# ESP32_Dev_Board.net
KiCad netlist of a schematic drawn in EasyEDA Pro
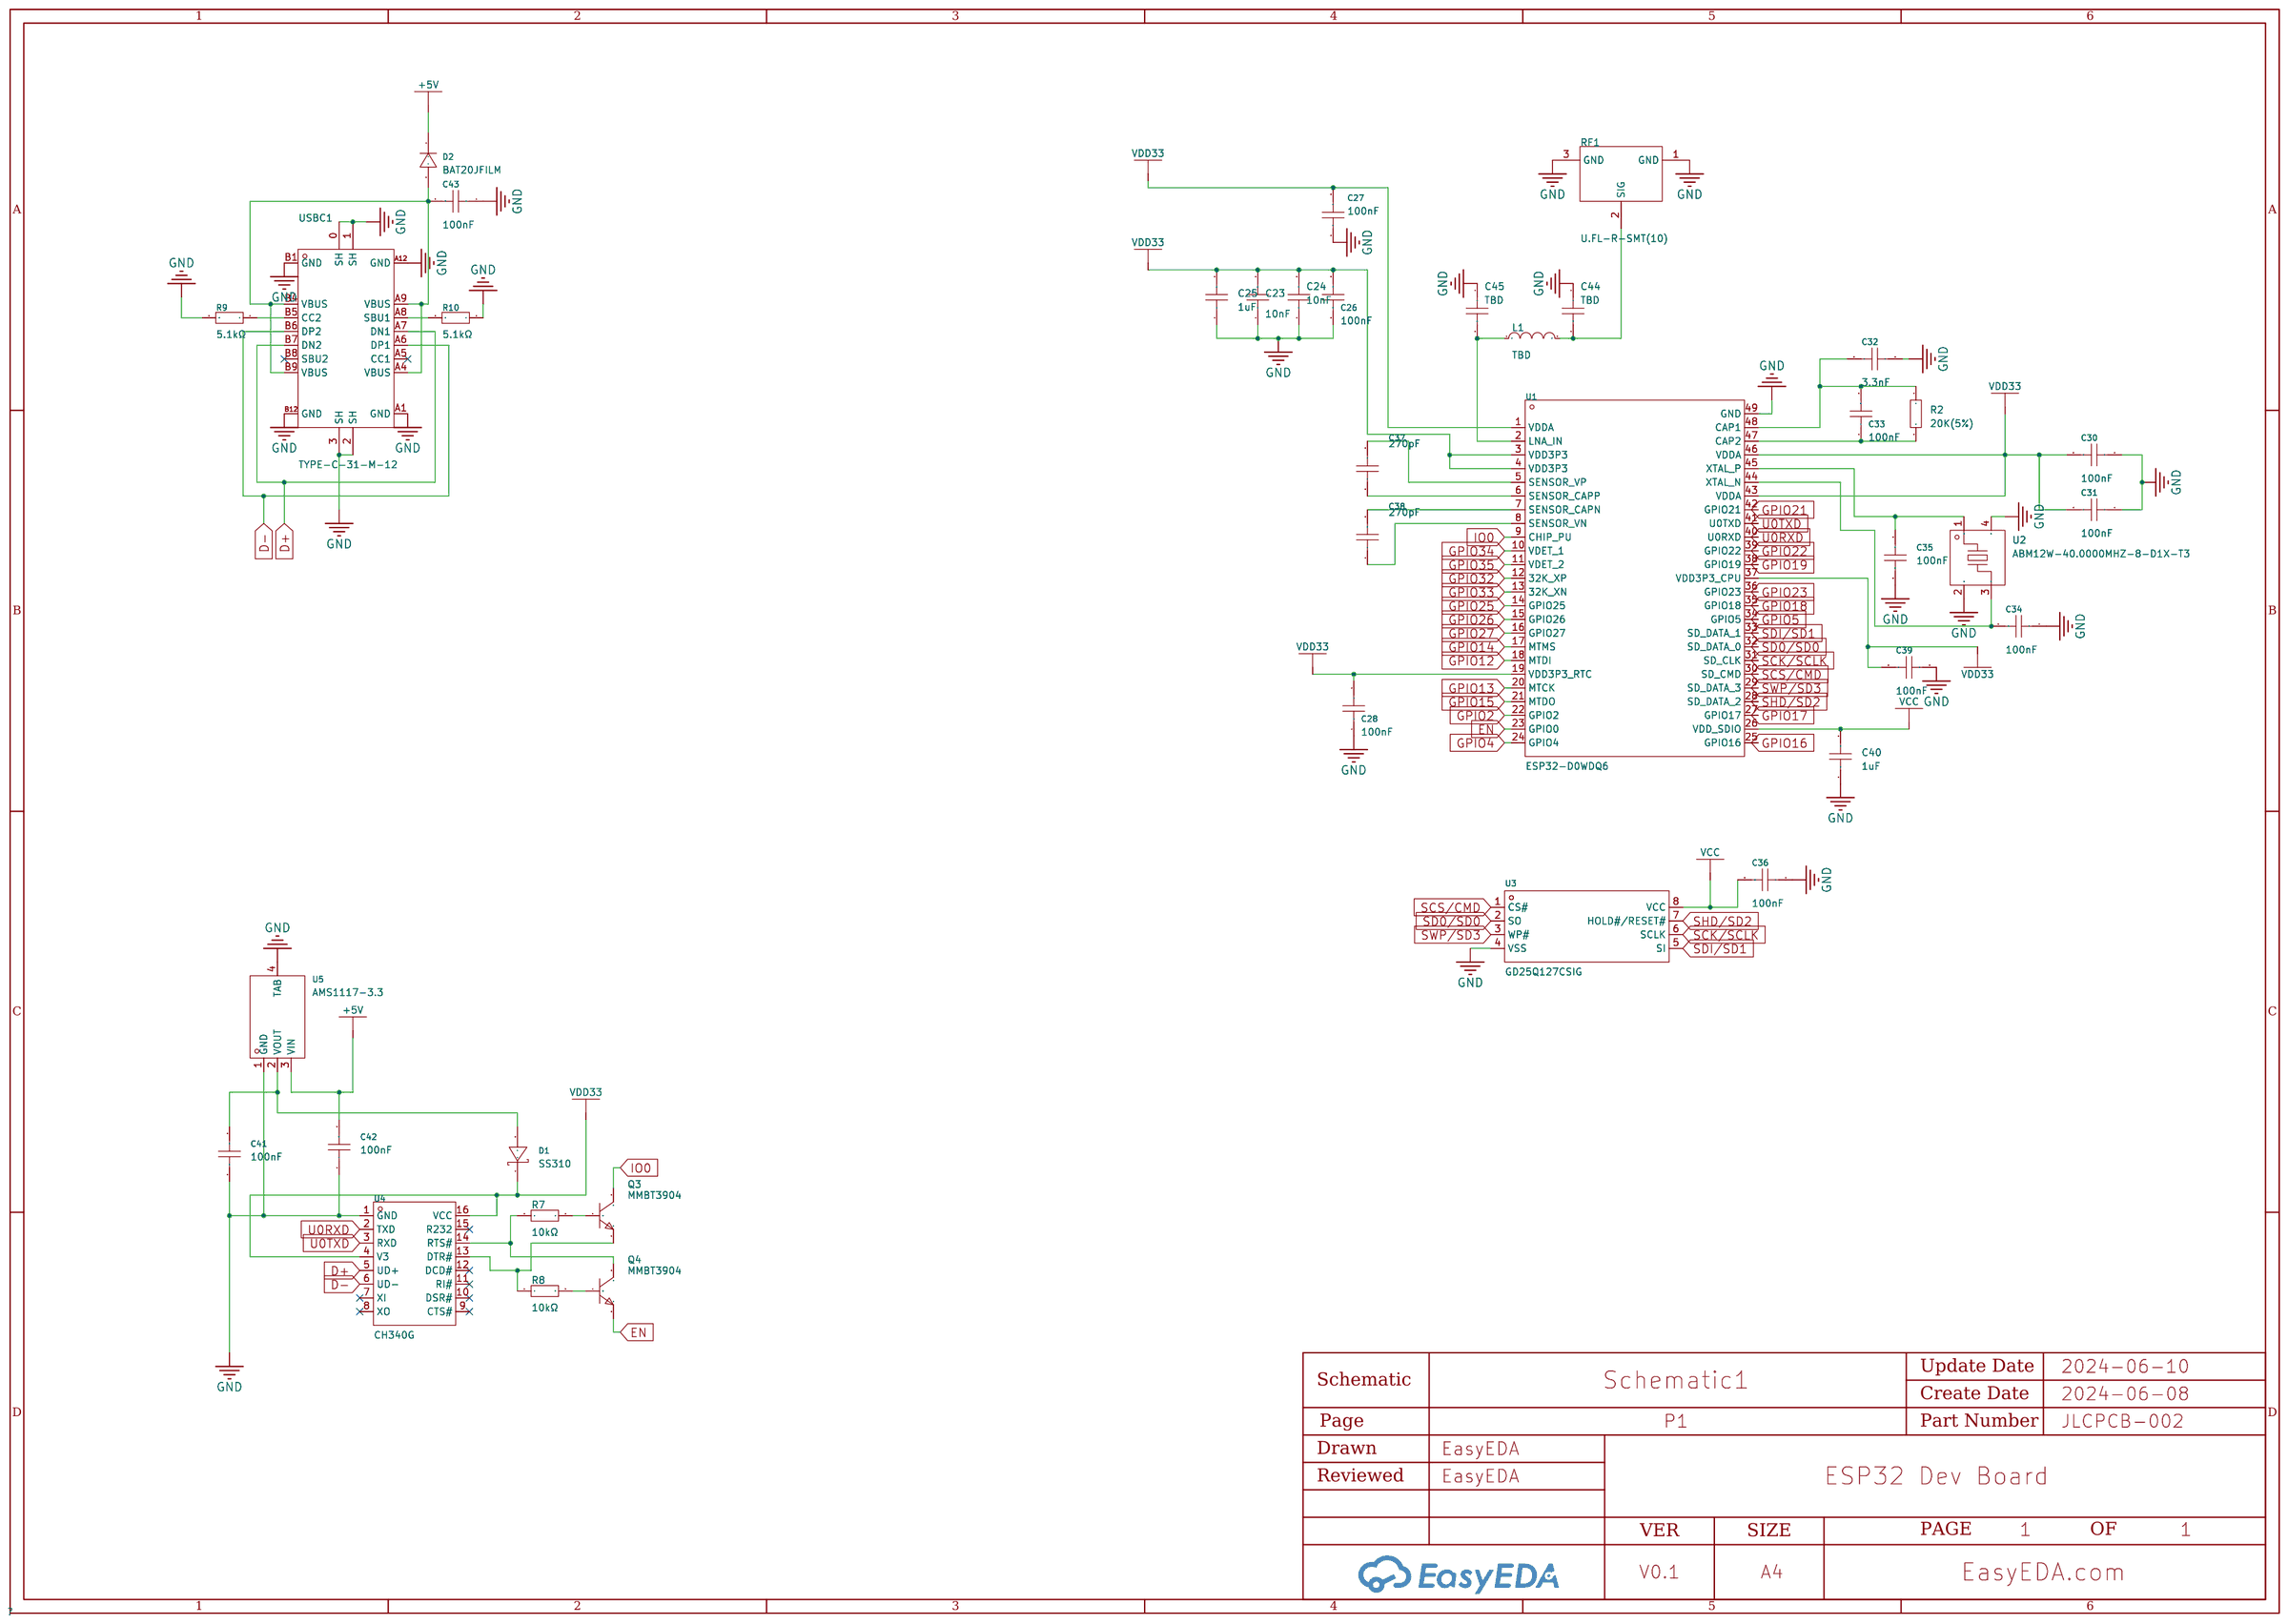
[diagram p0: schematic sheet]

(export (version "E")
  (design (tool "Eeschema 10.0.6"))
  (components
    (comp (ref "C23")
      (value "10nF")
      (footprint "easyedapro:C0402")
      (fields (field (name "Manufacturer Part") "0402B103K160NT") (field (name "Manufacturer") "FH(风华)"))
      (libsource (lib "easyedapro") (part "0402B103K160NT"))
    )
    (comp (ref "C24")
      (value "10nF")
      (footprint "easyedapro:C0402")
      (fields (field (name "Manufacturer Part") "0402B103K160NT") (field (name "Manufacturer") "FH(风华)"))
      (libsource (lib "easyedapro") (part "0402B103K160NT"))
    )
    (comp (ref "C25")
      (value "1uF")
      (footprint "easyedapro:C0402")
      (fields
        (field (name "Manufacturer Part") "C0402X5R105K350NT")
        (field (name "Manufacturer") "SANYEAR(叁叶源)")
      )
      (libsource (lib "easyedapro") (part "C0402X5R105K350NT"))
    )
    (comp (ref "C26")
      (value "100nF")
      (footprint "easyedapro:C0402")
      (fields
        (field (name "Manufacturer Part") "CT41G-0402-2X1-16V-0.1μF-K(N)")
        (field (name "Manufacturer") "TORCH(火炬)")
      )
      (libsource (lib "easyedapro") (part "CT41G-0402-2X1-16V-0.1μF-K(N)"))
    )
    (comp (ref "C27")
      (value "100nF")
      (footprint "easyedapro:C0402")
      (fields
        (field (name "Manufacturer Part") "CT41G-0402-2X1-16V-0.1μF-K(N)")
        (field (name "Manufacturer") "TORCH(火炬)")
      )
      (libsource (lib "easyedapro") (part "CT41G-0402-2X1-16V-0.1μF-K(N)"))
    )
    (comp (ref "C28")
      (value "100nF")
      (footprint "easyedapro:C0402")
      (fields
        (field (name "Manufacturer Part") "CT41G-0402-2X1-16V-0.1μF-K(N)")
        (field (name "Manufacturer") "TORCH(火炬)")
      )
      (libsource (lib "easyedapro") (part "CT41G-0402-2X1-16V-0.1μF-K(N)"))
    )
    (comp (ref "C30")
      (value "100nF")
      (footprint "easyedapro:C0402")
      (fields
        (field (name "Manufacturer Part") "CT41G-0402-2X1-16V-0.1μF-K(N)")
        (field (name "Manufacturer") "TORCH(火炬)")
      )
      (libsource (lib "easyedapro") (part "CT41G-0402-2X1-16V-0.1μF-K(N)"))
    )
    (comp (ref "C31")
      (value "100nF")
      (footprint "easyedapro:C0402")
      (fields
        (field (name "Manufacturer Part") "CT41G-0402-2X1-16V-0.1μF-K(N)")
        (field (name "Manufacturer") "TORCH(火炬)")
      )
      (libsource (lib "easyedapro") (part "CT41G-0402-2X1-16V-0.1μF-K(N)"))
    )
    (comp (ref "C32")
      (value "3.3nF")
      (footprint "easyedapro:C0402")
      (fields (field (name "Manufacturer Part") "04025C332KAT2A") (field (name "Manufacturer") "Kyocera AVX"))
      (libsource (lib "easyedapro") (part "04025C332KAT2A"))
    )
    (comp (ref "C33")
      (value "100nF")
      (footprint "easyedapro:C0402")
      (fields
        (field (name "Manufacturer Part") "CT41G-0402-2X1-16V-0.1μF-K(N)")
        (field (name "Manufacturer") "TORCH(火炬)")
      )
      (libsource (lib "easyedapro") (part "CT41G-0402-2X1-16V-0.1μF-K(N)"))
    )
    (comp (ref "C34")
      (value "100nF")
      (footprint "easyedapro:C0402")
      (fields
        (field (name "Manufacturer Part") "CT41G-0402-2X1-16V-0.1μF-K(N)")
        (field (name "Manufacturer") "TORCH(火炬)")
      )
      (libsource (lib "easyedapro") (part "CT41G-0402-2X1-16V-0.1μF-K(N)"))
    )
    (comp (ref "C35")
      (value "100nF")
      (footprint "easyedapro:C0402")
      (fields
        (field (name "Manufacturer Part") "CT41G-0402-2X1-16V-0.1μF-K(N)")
        (field (name "Manufacturer") "TORCH(火炬)")
      )
      (libsource (lib "easyedapro") (part "CT41G-0402-2X1-16V-0.1μF-K(N)"))
    )
    (comp (ref "C36")
      (value "100nF")
      (footprint "easyedapro:C0402")
      (fields
        (field (name "Manufacturer Part") "CT41G-0402-2X1-16V-0.1μF-K(N)")
        (field (name "Manufacturer") "TORCH(火炬)")
      )
      (libsource (lib "easyedapro") (part "CT41G-0402-2X1-16V-0.1μF-K(N)"))
    )
    (comp (ref "C37")
      (value "270pF")
      (footprint "easyedapro:C0402")
      (fields (field (name "Manufacturer Part") "0402N271J500CT") (field (name "Manufacturer") "Walsin(华新科)"))
      (libsource (lib "easyedapro") (part "0402N271J500CT"))
    )
    (comp (ref "C38")
      (value "270pF")
      (footprint "easyedapro:C0402")
      (fields (field (name "Manufacturer Part") "0402N271J500CT") (field (name "Manufacturer") "Walsin(华新科)"))
      (libsource (lib "easyedapro") (part "0402N271J500CT"))
    )
    (comp (ref "C39")
      (value "100nF")
      (footprint "easyedapro:C0402")
      (fields
        (field (name "Manufacturer Part") "CT41G-0402-2X1-16V-0.1μF-K(N)")
        (field (name "Manufacturer") "TORCH(火炬)")
      )
      (libsource (lib "easyedapro") (part "CT41G-0402-2X1-16V-0.1μF-K(N)"))
    )
    (comp (ref "C40")
      (value "1uF")
      (footprint "easyedapro:C0402")
      (fields
        (field (name "Manufacturer Part") "C0402X5R105K350NT")
        (field (name "Manufacturer") "SANYEAR(叁叶源)")
      )
      (libsource (lib "easyedapro") (part "C0402X5R105K350NT"))
    )
    (comp (ref "C41")
      (value "100nF")
      (footprint "easyedapro:C0402")
      (fields
        (field (name "Manufacturer Part") "CT41G-0402-2X1-16V-0.1μF-K(N)")
        (field (name "Manufacturer") "TORCH(火炬)")
      )
      (libsource (lib "easyedapro") (part "CT41G-0402-2X1-16V-0.1μF-K(N)"))
    )
    (comp (ref "C42")
      (value "100nF")
      (footprint "easyedapro:C0402")
      (fields
        (field (name "Manufacturer Part") "CT41G-0402-2X1-16V-0.1μF-K(N)")
        (field (name "Manufacturer") "TORCH(火炬)")
      )
      (libsource (lib "easyedapro") (part "CT41G-0402-2X1-16V-0.1μF-K(N)"))
    )
    (comp (ref "C43")
      (value "100nF")
      (footprint "easyedapro:C0402")
      (fields
        (field (name "Manufacturer Part") "CT41G-0402-2X1-16V-0.1μF-K(N)")
        (field (name "Manufacturer") "TORCH(火炬)")
      )
      (libsource (lib "easyedapro") (part "CT41G-0402-2X1-16V-0.1μF-K(N)"))
    )
    (comp (ref "C44")
      (value "TBD")
      (footprint "easyedapro:C0603")
      (libsource (lib "easyedapro") (part "CAP"))
    )
    (comp (ref "C45")
      (value "TBD")
      (footprint "easyedapro:C0603")
      (libsource (lib "easyedapro") (part "CAP"))
    )
    (comp (ref "D1")
      (value "SS310")
      (footprint "easyedapro:SMA_L4.4-W2.8-LS5.4-RD")
      (fields (field (name "Manufacturer") "晶导微电子"))
      (libsource (lib "easyedapro") (part "SS310_C116705"))
    )
    (comp (ref "D2")
      (value "BAT20JFILM")
      (footprint "easyedapro:SOD-323_L1.8-W1.3-LS2.5-RD")
      (fields (field (name "Manufacturer") "ST(意法半导体)"))
      (libsource (lib "easyedapro") (part "BAT20JFILM"))
    )
    (comp (ref "L1") (value "TBD") (footprint "easyedapro:L0603") (libsource (lib "easyedapro") (part "电感")))
    (comp (ref "Q3")
      (value "MMBT3904")
      (footprint "easyedapro:SOT-23-3_L2.9-W1.3-P1.90-LS2.4-BR")
      (fields (field (name "Manufacturer") "FMS(美丽微)"))
      (libsource (lib "easyedapro") (part "MMBT3904_C163254"))
    )
    (comp (ref "Q4")
      (value "MMBT3904")
      (footprint "easyedapro:SOT-23-3_L2.9-W1.3-P1.90-LS2.4-BR")
      (fields (field (name "Manufacturer") "FMS(美丽微)"))
      (libsource (lib "easyedapro") (part "MMBT3904_C163254"))
    )
    (comp (ref "R2")
      (value "20K(5%)")
      (footprint "easyedapro:R0603")
      (libsource (lib "easyedapro") (part "Res"))
    )
    (comp (ref "R7")
      (value "10kΩ")
      (footprint "easyedapro:R0402")
      (fields (field (name "Manufacturer Part") "RMC040210KFN") (field (name "Manufacturer") "Tyohm(幸亚电阻)"))
      (libsource (lib "easyedapro") (part "RMC040210K1%N"))
    )
    (comp (ref "R8")
      (value "10kΩ")
      (footprint "easyedapro:R0402")
      (fields (field (name "Manufacturer Part") "RMC040210KFN") (field (name "Manufacturer") "Tyohm(幸亚电阻)"))
      (libsource (lib "easyedapro") (part "RMC040210K1%N"))
    )
    (comp (ref "R9")
      (value "5.1kΩ")
      (footprint "easyedapro:R0402")
      (fields (field (name "Manufacturer Part") "RMC04025.1K1%N") (field (name "Manufacturer") "Tyohm(幸亚电阻)"))
      (libsource (lib "easyedapro") (part "RMC04025.1K1%N"))
    )
    (comp (ref "R10")
      (value "5.1kΩ")
      (footprint "easyedapro:R0402")
      (fields (field (name "Manufacturer Part") "RMC04025.1K1%N") (field (name "Manufacturer") "Tyohm(幸亚电阻)"))
      (libsource (lib "easyedapro") (part "RMC04025.1K1%N"))
    )
    (comp (ref "RF1")
      (value "U.FL-R-SMT(10)")
      (footprint "easyedapro:ANT-SMD_UFL-R-SMT01")
      (fields (field (name "Manufacturer") "HRS(广濑)"))
      (libsource (lib "easyedapro") (part "U.FL-R-SMT(10)"))
    )
    (comp (ref "U1")
      (value "ESP32-D0WDQ6")
      (footprint "easyedapro:QFN-48_L6.0-W6.0-P0.40-BL-EP3.8")
      (fields (field (name "Manufacturer") "ESPRESSIF(乐鑫)"))
      (libsource (lib "easyedapro") (part "ESP32-D0WDQ6"))
    )
    (comp (ref "U2")
      (value "ABM12W-40.0000MHZ-8-D1X-T3")
      (footprint "easyedapro:CRYSTAL-SMD_4P-L1.6-W1.2-BL")
      (libsource (lib "easyedapro") (part "ABM12W-40.0000MHZ-8-D1X-T3"))
    )
    (comp (ref "U3")
      (value "GD25Q127CSIG")
      (footprint "easyedapro:SOP-8_L5.3-W5.3-P1.27-LS8.0-BL")
      (fields (field (name "Manufacturer") "GigaDevice(兆易创新)"))
      (libsource (lib "easyedapro") (part "GD25Q127CSIG"))
    )
    (comp (ref "U4")
      (value "CH340G")
      (footprint "easyedapro:SOIC-16_L9.9-W3.9-P1.27-LS6.0-BL")
      (fields (field (name "Manufacturer") "WCH(南京沁恒)"))
      (libsource (lib "easyedapro") (part "CH340G"))
    )
    (comp (ref "U5")
      (value "AMS1117-3.3")
      (footprint "easyedapro:SOT-223-3_L6.5-W3.4-P2.30-LS7.0-BR")
      (fields (field (name "Manufacturer") "PUOLOP(迪浦)"))
      (libsource (lib "easyedapro") (part "AMS1117-3.3_C351784"))
    )
    (comp (ref "USBC1")
      (value "TYPE-C-31-M-12")
      (footprint "easyedapro:USB-C_SMD-TYPE-C-31-M-12")
      (fields (field (name "Manufacturer") "韩国韩荣"))
      (libsource (lib "easyedapro") (part "TYPE-C-31-M-12"))
    )
  )
  (nets
    (net (code "1") (name "+5V") (class "Default")
      (node (ref "C42") (pin "2") (pinfunction "2_2") (pintype "input"))
      (node (ref "D2") (pin "1") (pinfunction "K_1") (pintype "input"))
      (node (ref "U5") (pin "3") (pinfunction "VIN_3") (pintype "input"))
    )
    (net (code "2") (name "D+") (class "Default")
      (node (ref "U4") (pin "5") (pinfunction "UD+_5") (pintype "input"))
      (node (ref "USBC1") (pin "A7") (pinfunction "DN1_A7") (pintype "unspecified"))
      (node (ref "USBC1") (pin "B7") (pinfunction "DN2_B7") (pintype "unspecified"))
    )
    (net (code "3") (name "D-") (class "Default")
      (node (ref "U4") (pin "6") (pinfunction "UD-_6") (pintype "input"))
      (node (ref "USBC1") (pin "A6") (pinfunction "DP1_A6") (pintype "unspecified"))
      (node (ref "USBC1") (pin "B6") (pinfunction "DP2_B6") (pintype "unspecified"))
    )
    (net (code "4") (name "EN") (class "Default")
      (node (ref "Q4") (pin "2") (pinfunction "E_2") (pintype "unspecified"))
      (node (ref "U1") (pin "23") (pinfunction "GPIO0_23") (pintype "input"))
    )
    (net (code "5") (name "GND") (class "Default")
      (node (ref "C23") (pin "1") (pinfunction "1_1") (pintype "unspecified"))
      (node (ref "C24") (pin "1") (pinfunction "1_1") (pintype "unspecified"))
      (node (ref "C25") (pin "1") (pinfunction "1_1") (pintype "input"))
      (node (ref "C26") (pin "1") (pinfunction "1_1") (pintype "input"))
      (node (ref "C27") (pin "1") (pinfunction "1_1") (pintype "input"))
      (node (ref "C28") (pin "1") (pinfunction "1_1") (pintype "input"))
      (node (ref "C30") (pin "1") (pinfunction "1_1") (pintype "input"))
      (node (ref "C31") (pin "1") (pinfunction "1_1") (pintype "input"))
      (node (ref "C32") (pin "1") (pinfunction "1_1") (pintype "input"))
      (node (ref "C34") (pin "1") (pinfunction "1_1") (pintype "input"))
      (node (ref "C35") (pin "2") (pinfunction "2_2") (pintype "input"))
      (node (ref "C36") (pin "1") (pinfunction "1_1") (pintype "input"))
      (node (ref "C39") (pin "1") (pinfunction "1_1") (pintype "input"))
      (node (ref "C40") (pin "1") (pinfunction "1_1") (pintype "input"))
      (node (ref "C41") (pin "1") (pinfunction "1_1") (pintype "input"))
      (node (ref "C42") (pin "1") (pinfunction "1_1") (pintype "input"))
      (node (ref "C43") (pin "1") (pinfunction "1_1") (pintype "input"))
      (node (ref "C44") (pin "1") (pinfunction "1_1") (pintype "input"))
      (node (ref "C45") (pin "1") (pinfunction "1_1") (pintype "input"))
      (node (ref "R10") (pin "1") (pinfunction "1_1") (pintype "input"))
      (node (ref "R9") (pin "2") (pinfunction "2_2") (pintype "input"))
      (node (ref "RF1") (pin "1") (pinfunction "GND_1") (pintype "unspecified"))
      (node (ref "RF1") (pin "3") (pinfunction "GND_3") (pintype "unspecified"))
      (node (ref "U1") (pin "49") (pinfunction "GND_49") (pintype "input"))
      (node (ref "U2") (pin "2") (pinfunction "GND_2") (pintype "input"))
      (node (ref "U2") (pin "4") (pinfunction "GND_4") (pintype "input"))
      (node (ref "U3") (pin "4") (pinfunction "VSS_4") (pintype "input"))
      (node (ref "U4") (pin "1") (pinfunction "GND_1") (pintype "input"))
      (node (ref "U5") (pin "1") (pinfunction "GND_1") (pintype "input"))
      (node (ref "U5") (pin "4") (pinfunction "TAB_4") (pintype "input"))
      (node (ref "USBC1") (pin "0") (pinfunction "SH_0") (pintype "unspecified"))
      (node (ref "USBC1") (pin "1") (pinfunction "SH_1") (pintype "unspecified"))
      (node (ref "USBC1") (pin "2") (pinfunction "SH_2") (pintype "unspecified"))
      (node (ref "USBC1") (pin "3") (pinfunction "SH_3") (pintype "unspecified"))
      (node (ref "USBC1") (pin "A1") (pinfunction "GND_A1") (pintype "unspecified"))
      (node (ref "USBC1") (pin "A12") (pinfunction "GND_A12") (pintype "unspecified"))
      (node (ref "USBC1") (pin "B1") (pinfunction "GND_B1") (pintype "unspecified"))
      (node (ref "USBC1") (pin "B12") (pinfunction "GND_B12") (pintype "unspecified"))
    )
    (net (code "6") (name "GPIO2") (class "Default")
      (node (ref "U1") (pin "22") (pinfunction "GPIO2_22") (pintype "input"))
    )
    (net (code "7") (name "GPIO4") (class "Default")
      (node (ref "U1") (pin "24") (pinfunction "GPIO4_24") (pintype "input"))
    )
    (net (code "8") (name "GPIO5") (class "Default")
      (node (ref "U1") (pin "34") (pinfunction "GPIO5_34") (pintype "input"))
    )
    (net (code "9") (name "GPIO12") (class "Default")
      (node (ref "U1") (pin "18") (pinfunction "MTDI_18") (pintype "input"))
    )
    (net (code "10") (name "GPIO13") (class "Default")
      (node (ref "U1") (pin "20") (pinfunction "MTCK_20") (pintype "input"))
    )
    (net (code "11") (name "GPIO14") (class "Default")
      (node (ref "U1") (pin "17") (pinfunction "MTMS_17") (pintype "input"))
    )
    (net (code "12") (name "GPIO15") (class "Default")
      (node (ref "U1") (pin "21") (pinfunction "MTDO_21") (pintype "input"))
    )
    (net (code "13") (name "GPIO16") (class "Default")
      (node (ref "U1") (pin "25") (pinfunction "GPIO16_25") (pintype "input"))
    )
    (net (code "14") (name "GPIO17") (class "Default")
      (node (ref "U1") (pin "27") (pinfunction "GPIO17_27") (pintype "input"))
    )
    (net (code "15") (name "GPIO18") (class "Default")
      (node (ref "U1") (pin "35") (pinfunction "GPIO18_35") (pintype "input"))
    )
    (net (code "16") (name "GPIO19") (class "Default")
      (node (ref "U1") (pin "38") (pinfunction "GPIO19_38") (pintype "input"))
    )
    (net (code "17") (name "GPIO21") (class "Default")
      (node (ref "U1") (pin "42") (pinfunction "GPIO21_42") (pintype "input"))
    )
    (net (code "18") (name "GPIO22") (class "Default")
      (node (ref "U1") (pin "39") (pinfunction "GPIO22_39") (pintype "input"))
    )
    (net (code "19") (name "GPIO23") (class "Default")
      (node (ref "U1") (pin "36") (pinfunction "GPIO23_36") (pintype "input"))
    )
    (net (code "20") (name "GPIO25") (class "Default")
      (node (ref "U1") (pin "14") (pinfunction "GPIO25_14") (pintype "input"))
    )
    (net (code "21") (name "GPIO26") (class "Default")
      (node (ref "U1") (pin "15") (pinfunction "GPIO26_15") (pintype "input"))
    )
    (net (code "22") (name "GPIO27") (class "Default")
      (node (ref "U1") (pin "16") (pinfunction "GPIO27_16") (pintype "input"))
    )
    (net (code "23") (name "GPIO32") (class "Default")
      (node (ref "U1") (pin "12") (pinfunction "32K_XP_12") (pintype "input"))
    )
    (net (code "24") (name "GPIO33") (class "Default")
      (node (ref "U1") (pin "13") (pinfunction "32K_XN_13") (pintype "input"))
    )
    (net (code "25") (name "GPIO34") (class "Default")
      (node (ref "U1") (pin "10") (pinfunction "VDET_1_10") (pintype "input"))
    )
    (net (code "26") (name "GPIO35") (class "Default")
      (node (ref "U1") (pin "11") (pinfunction "VDET_2_11") (pintype "input"))
    )
    (net (code "27") (name "IO0") (class "Default")
      (node (ref "Q3") (pin "3") (pinfunction "C_3") (pintype "unspecified"))
      (node (ref "U1") (pin "9") (pinfunction "CHIP_PU_9") (pintype "input"))
    )
    (net (code "28") (name "Net-(D1-A)") (class "Default")
      (node (ref "C41") (pin "2") (pinfunction "2_2") (pintype "input"))
      (node (ref "D1") (pin "2") (pinfunction "A_2") (pintype "input"))
      (node (ref "U5") (pin "2") (pinfunction "VOUT_2") (pintype "input"))
    )
    (net (code "29") (name "Net-(D2-A)") (class "Default")
      (node (ref "C43") (pin "2") (pinfunction "2_2") (pintype "input"))
      (node (ref "D2") (pin "2") (pinfunction "A_2") (pintype "input"))
      (node (ref "USBC1") (pin "A4") (pinfunction "VBUS_A4") (pintype "unspecified"))
      (node (ref "USBC1") (pin "A9") (pinfunction "VBUS_A9") (pintype "unspecified"))
      (node (ref "USBC1") (pin "B4") (pinfunction "VBUS_B4") (pintype "unspecified"))
      (node (ref "USBC1") (pin "B9") (pinfunction "VBUS_B9") (pintype "unspecified"))
    )
    (net (code "30") (name "Net-(Q3-B)") (class "Default")
      (node (ref "Q3") (pin "1") (pinfunction "B_1") (pintype "unspecified"))
      (node (ref "R7") (pin "2") (pinfunction "2_2") (pintype "input"))
    )
    (net (code "31") (name "Net-(Q3-E)") (class "Default")
      (node (ref "Q3") (pin "2") (pinfunction "E_2") (pintype "unspecified"))
      (node (ref "R8") (pin "1") (pinfunction "1_1") (pintype "input"))
      (node (ref "U4") (pin "13") (pinfunction "DTR#_13") (pintype "input"))
    )
    (net (code "32") (name "Net-(Q4-B)") (class "Default")
      (node (ref "Q4") (pin "1") (pinfunction "B_1") (pintype "unspecified"))
      (node (ref "R8") (pin "2") (pinfunction "2_2") (pintype "input"))
    )
    (net (code "33") (name "Net-(Q4-C)") (class "Default")
      (node (ref "Q4") (pin "3") (pinfunction "C_3") (pintype "unspecified"))
      (node (ref "R7") (pin "1") (pinfunction "1_1") (pintype "input"))
      (node (ref "U4") (pin "14") (pinfunction "RTS#_14") (pintype "input"))
    )
    (net (code "34") (name "Net-(RF1-SIG)") (class "Default")
      (node (ref "C44") (pin "2") (pinfunction "2_2") (pintype "input"))
      (node (ref "L1") (pin "2") (pinfunction "2_2") (pintype "input"))
      (node (ref "RF1") (pin "2") (pinfunction "SIG_2") (pintype "unspecified"))
    )
    (net (code "35") (name "Net-(U1-CAP1)") (class "Default")
      (node (ref "C32") (pin "2") (pinfunction "2_2") (pintype "input"))
      (node (ref "C33") (pin "2") (pinfunction "2_2") (pintype "input"))
      (node (ref "R2") (pin "1") (pinfunction "1_1") (pintype "input"))
      (node (ref "U1") (pin "48") (pinfunction "CAP1_48") (pintype "input"))
    )
    (net (code "36") (name "Net-(U1-CAP2)") (class "Default")
      (node (ref "C33") (pin "1") (pinfunction "1_1") (pintype "input"))
      (node (ref "R2") (pin "2") (pinfunction "2_2") (pintype "input"))
      (node (ref "U1") (pin "47") (pinfunction "CAP2_47") (pintype "input"))
    )
    (net (code "37") (name "Net-(U1-LNA_IN)") (class "Default")
      (node (ref "C45") (pin "2") (pinfunction "2_2") (pintype "input"))
      (node (ref "L1") (pin "1") (pinfunction "1_1") (pintype "input"))
      (node (ref "U1") (pin "2") (pinfunction "LNA_IN_2") (pintype "input"))
    )
    (net (code "38") (name "Net-(U1-SENSOR_CAPN)") (class "Default")
      (node (ref "C38") (pin "2") (pinfunction "2_2") (pintype "input"))
      (node (ref "U1") (pin "7") (pinfunction "SENSOR_CAPN_7") (pintype "input"))
    )
    (net (code "39") (name "Net-(U1-SENSOR_CAPP)") (class "Default")
      (node (ref "C37") (pin "1") (pinfunction "1_1") (pintype "input"))
      (node (ref "U1") (pin "6") (pinfunction "SENSOR_CAPP_6") (pintype "input"))
    )
    (net (code "40") (name "Net-(U1-SENSOR_VN)") (class "Default")
      (node (ref "C38") (pin "1") (pinfunction "1_1") (pintype "input"))
      (node (ref "U1") (pin "8") (pinfunction "SENSOR_VN_8") (pintype "input"))
    )
    (net (code "41") (name "Net-(U1-SENSOR_VP)") (class "Default")
      (node (ref "C37") (pin "2") (pinfunction "2_2") (pintype "input"))
      (node (ref "U1") (pin "5") (pinfunction "SENSOR_VP_5") (pintype "input"))
    )
    (net (code "42") (name "Net-(U1-XTAL_N)") (class "Default")
      (node (ref "C34") (pin "2") (pinfunction "2_2") (pintype "input"))
      (node (ref "U1") (pin "44") (pinfunction "XTAL_N_44") (pintype "input"))
      (node (ref "U2") (pin "3") (pinfunction "OUT_3") (pintype "input"))
    )
    (net (code "43") (name "Net-(U1-XTAL_P)") (class "Default")
      (node (ref "C35") (pin "1") (pinfunction "1_1") (pintype "input"))
      (node (ref "U1") (pin "45") (pinfunction "XTAL_P_45") (pintype "input"))
      (node (ref "U2") (pin "1") (pinfunction "IN_1") (pintype "input"))
    )
    (net (code "44") (name "Net-(USBC1-CC2)") (class "Default")
      (node (ref "R9") (pin "1") (pinfunction "1_1") (pintype "input"))
      (node (ref "USBC1") (pin "B5") (pinfunction "CC2_B5") (pintype "unspecified"))
    )
    (net (code "45") (name "Net-(USBC1-SBU1)") (class "Default")
      (node (ref "R10") (pin "2") (pinfunction "2_2") (pintype "input"))
      (node (ref "USBC1") (pin "A8") (pinfunction "SBU1_A8") (pintype "unspecified"))
    )
    (net (code "46") (name "SCK{slash}SCLK") (class "Default")
      (node (ref "U1") (pin "31") (pinfunction "SD_CLK_31") (pintype "input"))
      (node (ref "U3") (pin "6") (pinfunction "SCLK_6") (pintype "input"))
    )
    (net (code "47") (name "SCS{slash}CMD") (class "Default")
      (node (ref "U1") (pin "30") (pinfunction "SD_CMD_30") (pintype "input"))
      (node (ref "U3") (pin "1") (pinfunction "CS#_1") (pintype "input"))
    )
    (net (code "48") (name "SD0{slash}SD0") (class "Default")
      (node (ref "U1") (pin "32") (pinfunction "SD_DATA_0_32") (pintype "input"))
      (node (ref "U3") (pin "2") (pinfunction "SO_2") (pintype "input"))
    )
    (net (code "49") (name "SDI{slash}SD1") (class "Default")
      (node (ref "U1") (pin "33") (pinfunction "SD_DATA_1_33") (pintype "input"))
      (node (ref "U3") (pin "5") (pinfunction "SI_5") (pintype "input"))
    )
    (net (code "50") (name "SHD{slash}SD2") (class "Default")
      (node (ref "U1") (pin "28") (pinfunction "SD_DATA_2_28") (pintype "input"))
      (node (ref "U3") (pin "7") (pinfunction "HOLD#/RESET#_7") (pintype "input"))
    )
    (net (code "51") (name "SWP{slash}SD3") (class "Default")
      (node (ref "U1") (pin "29") (pinfunction "SD_DATA_3_29") (pintype "input"))
      (node (ref "U3") (pin "3") (pinfunction "WP#_3") (pintype "input"))
    )
    (net (code "52") (name "U0RXD") (class "Default")
      (node (ref "U1") (pin "40") (pinfunction "U0RXD_40") (pintype "input"))
      (node (ref "U4") (pin "2") (pinfunction "TXD_2") (pintype "input"))
    )
    (net (code "53") (name "U0TXD") (class "Default")
      (node (ref "U1") (pin "41") (pinfunction "U0TXD_41") (pintype "input"))
      (node (ref "U4") (pin "3") (pinfunction "RXD_3") (pintype "input"))
    )
    (net (code "54") (name "VCC") (class "Default")
      (node (ref "C36") (pin "2") (pinfunction "2_2") (pintype "input"))
      (node (ref "C40") (pin "2") (pinfunction "2_2") (pintype "input"))
      (node (ref "U1") (pin "26") (pinfunction "VDD_SDIO_26") (pintype "input"))
      (node (ref "U3") (pin "8") (pinfunction "VCC_8") (pintype "input"))
    )
    (net (code "55") (name "VDD33") (class "Default")
      (node (ref "C23") (pin "2") (pinfunction "2_2") (pintype "unspecified"))
      (node (ref "C24") (pin "2") (pinfunction "2_2") (pintype "unspecified"))
      (node (ref "C25") (pin "2") (pinfunction "2_2") (pintype "input"))
      (node (ref "C26") (pin "2") (pinfunction "2_2") (pintype "input"))
      (node (ref "C27") (pin "2") (pinfunction "2_2") (pintype "input"))
      (node (ref "C28") (pin "2") (pinfunction "2_2") (pintype "input"))
      (node (ref "C30") (pin "2") (pinfunction "2_2") (pintype "input"))
      (node (ref "C31") (pin "2") (pinfunction "2_2") (pintype "input"))
      (node (ref "C39") (pin "2") (pinfunction "2_2") (pintype "input"))
      (node (ref "D1") (pin "1") (pinfunction "K_1") (pintype "input"))
      (node (ref "U1") (pin "1") (pinfunction "VDDA_1") (pintype "input"))
      (node (ref "U1") (pin "19") (pinfunction "VDD3P3_RTC_19") (pintype "input"))
      (node (ref "U1") (pin "3") (pinfunction "VDD3P3_3") (pintype "input"))
      (node (ref "U1") (pin "37") (pinfunction "VDD3P3_CPU_37") (pintype "input"))
      (node (ref "U1") (pin "4") (pinfunction "VDD3P3_4") (pintype "input"))
      (node (ref "U1") (pin "43") (pinfunction "VDDA_43") (pintype "input"))
      (node (ref "U1") (pin "46") (pinfunction "VDDA_46") (pintype "input"))
      (node (ref "U4") (pin "16") (pinfunction "VCC_16") (pintype "input"))
      (node (ref "U4") (pin "4") (pinfunction "V3_4") (pintype "input"))
    )
    (net (code "56") (name "unconnected-(U4-CTS#-Pad9)") (class "Default")
      (node (ref "U4") (pin "9") (pinfunction "CTS#_9") (pintype "input+no_connect"))
    )
    (net (code "57") (name "unconnected-(U4-DCD#-Pad12)") (class "Default")
      (node (ref "U4") (pin "12") (pinfunction "DCD#_12") (pintype "input+no_connect"))
    )
    (net (code "58") (name "unconnected-(U4-DSR#-Pad10)") (class "Default")
      (node (ref "U4") (pin "10") (pinfunction "DSR#_10") (pintype "input+no_connect"))
    )
    (net (code "59") (name "unconnected-(U4-R232-Pad15)") (class "Default")
      (node (ref "U4") (pin "15") (pinfunction "R232_15") (pintype "input+no_connect"))
    )
    (net (code "60") (name "unconnected-(U4-RI#-Pad11)") (class "Default")
      (node (ref "U4") (pin "11") (pinfunction "RI#_11") (pintype "input+no_connect"))
    )
    (net (code "61") (name "unconnected-(U4-XI-Pad7)") (class "Default")
      (node (ref "U4") (pin "7") (pinfunction "XI_7") (pintype "input+no_connect"))
    )
    (net (code "62") (name "unconnected-(U4-XO-Pad8)") (class "Default")
      (node (ref "U4") (pin "8") (pinfunction "XO_8") (pintype "input+no_connect"))
    )
    (net (code "63") (name "unconnected-(USBC1-CC1-PadA5)") (class "Default")
      (node (ref "USBC1") (pin "A5") (pinfunction "CC1_A5") (pintype "unspecified+no_connect"))
    )
    (net (code "64") (name "unconnected-(USBC1-SBU2-PadB8)") (class "Default")
      (node (ref "USBC1") (pin "B8") (pinfunction "SBU2_B8") (pintype "unspecified+no_connect"))
    )
  )
)
